# SCH_555-timer-LED-Chaser_2025-11-26.net
KiCad netlist of a schematic drawn in EasyEDA
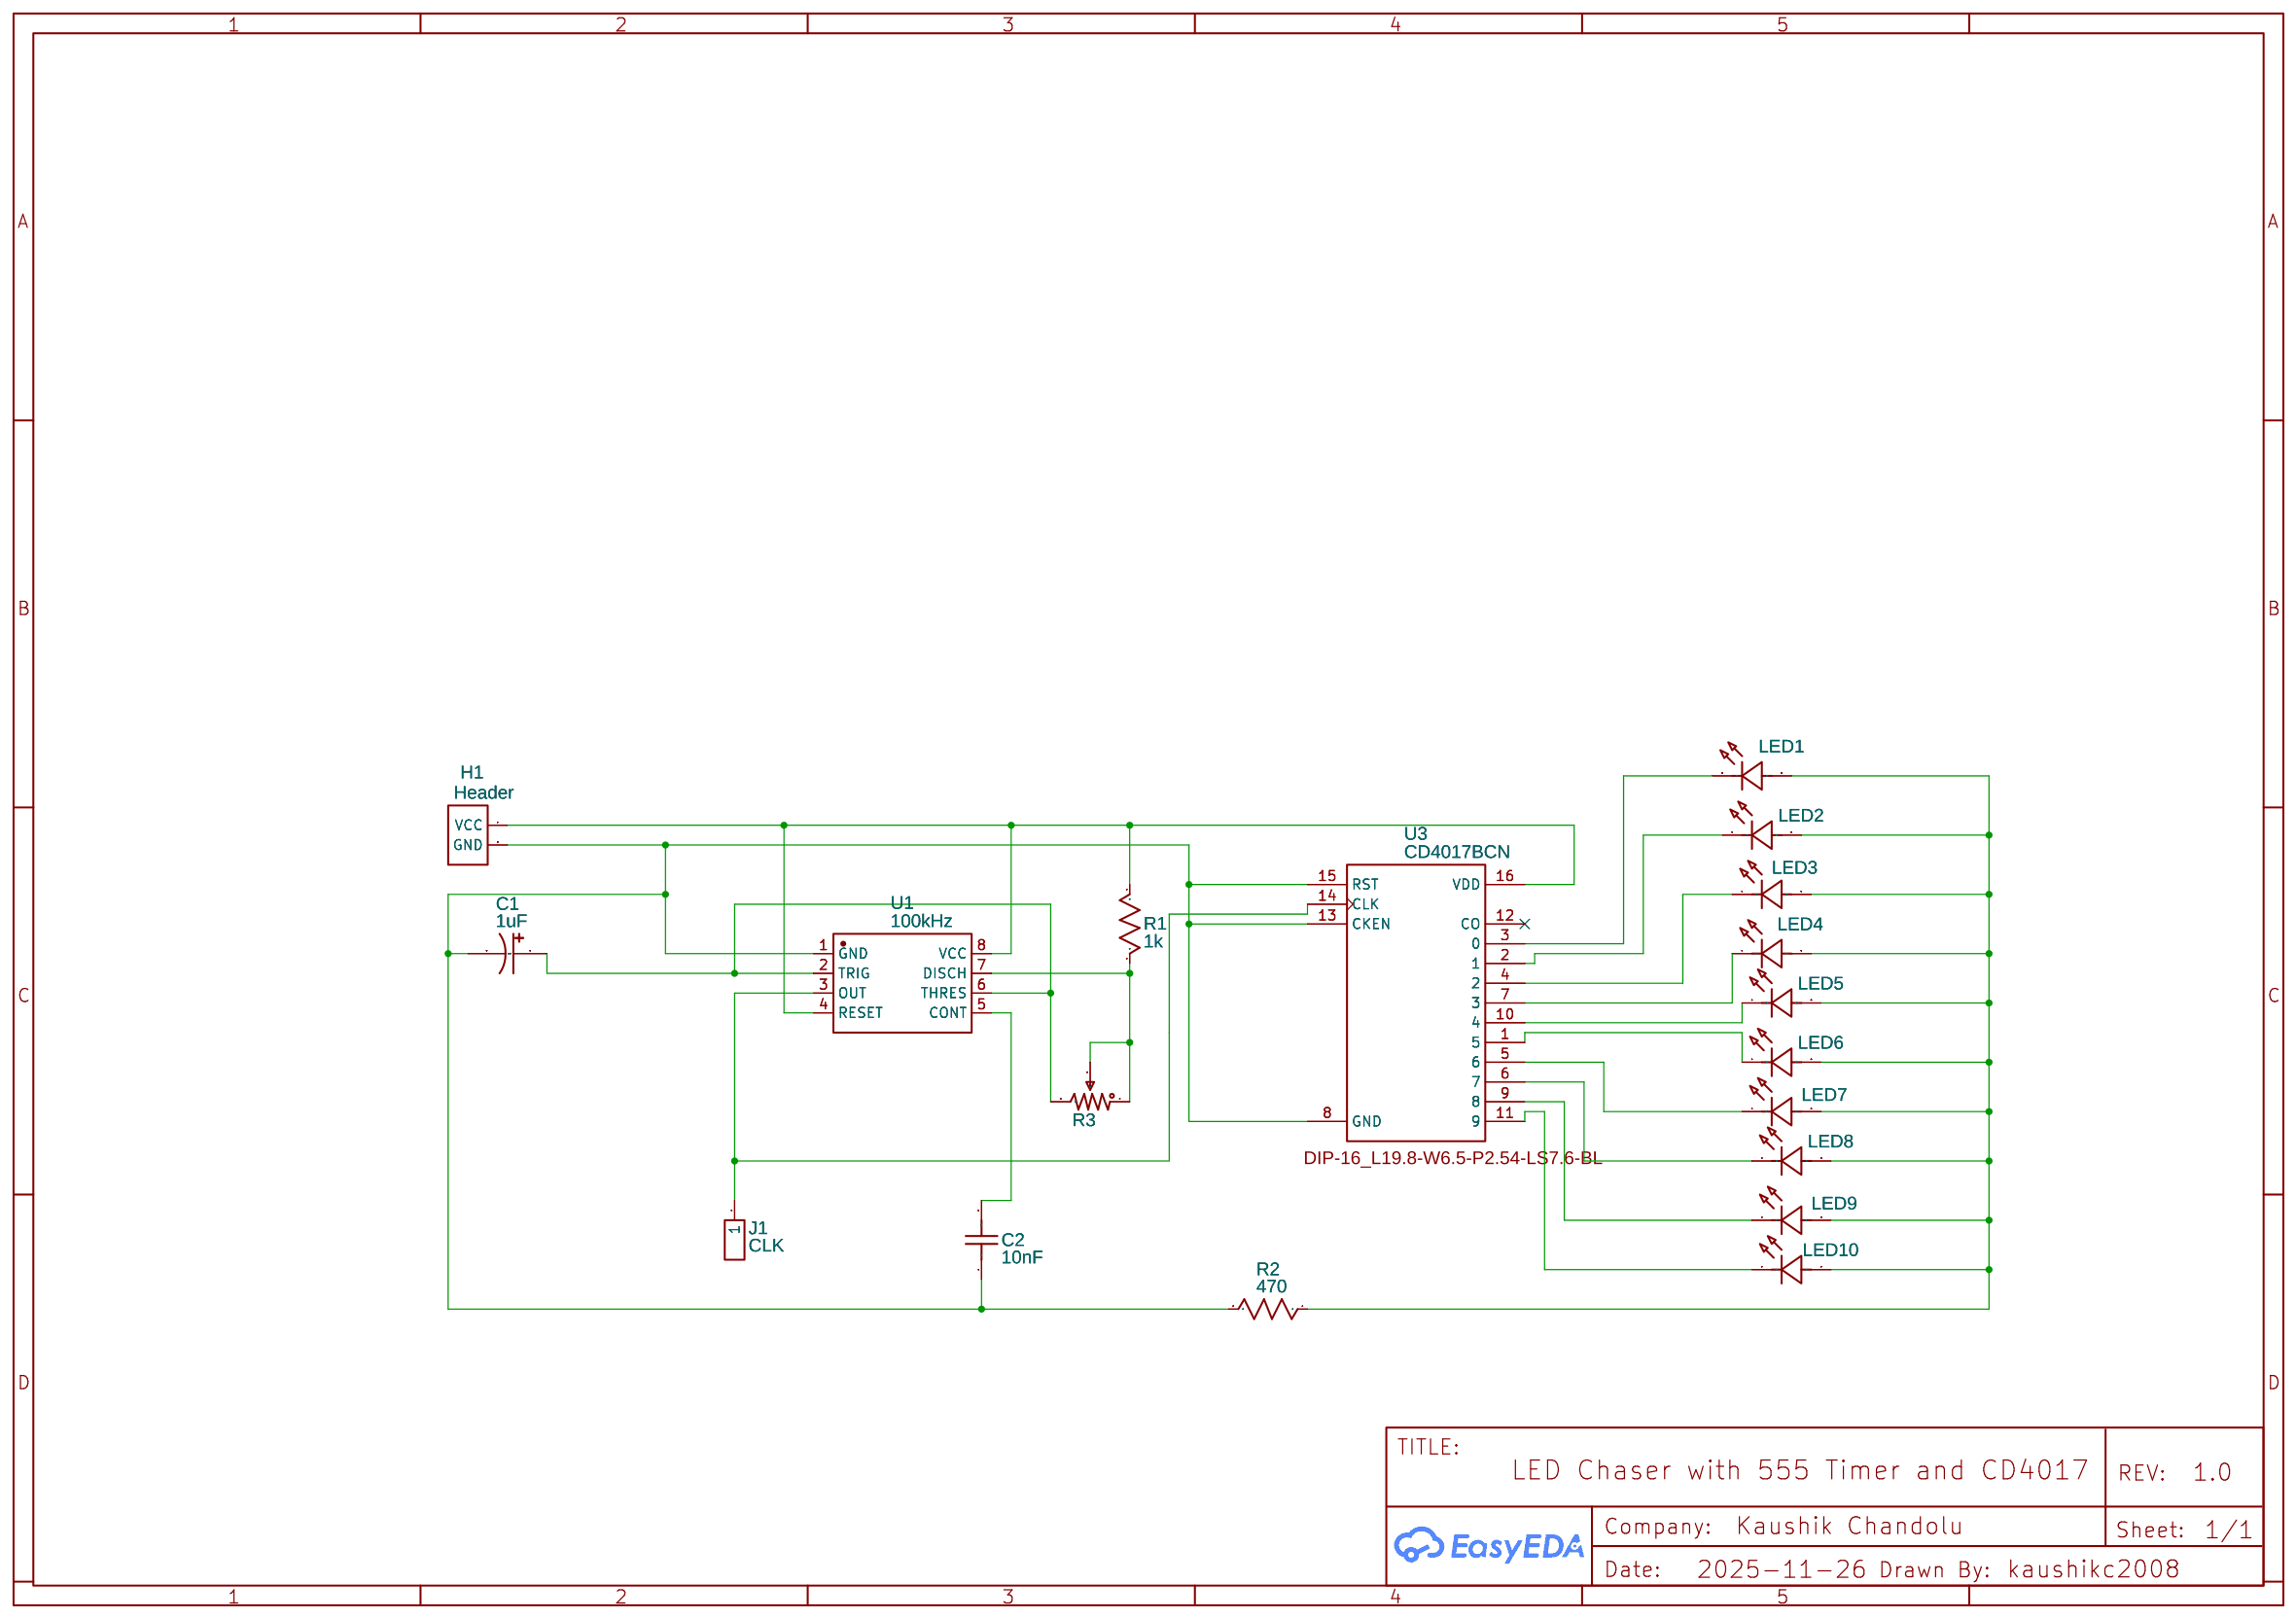
[diagram p0: schematic sheet]

(export (version "E")
  (design (tool "Eeschema 10.0.6"))
  (components
    (comp (ref "C1")
      (value "1uF")
      (fields (field (name "Manufacturer Part") "UVZ1H010MDD") (field (name "Manufacturer") "Nichicon(尼吉康)"))
      (libsource (lib "") (part "UVZ1H010MDD"))
    )
    (comp (ref "C2")
      (value "10nF")
      (fields
        (field (name "Manufacturer Part") "N09F1B103MN0B0S0N0")
        (field (name "Manufacturer") "Songtian Elec")
      )
      (libsource (lib "") (part "CAP 10nF HV"))
    )
    (comp (ref "H1") (value "Header") (libsource (lib "") (part "HEADER-FEMALE-2.54_1X2")))
    (comp (ref "J1") (value "CLK") (libsource (lib "") (part "HDR-M-2.54_1x1")))
    (comp (ref "LED1")
      (value "XL-502UWC")
      (fields (field (name "Manufacturer") "XINGLIGHT(成兴光)"))
      (libsource (lib "") (part "XL-502UWC"))
    )
    (comp (ref "LED2")
      (value "XL-502UWC")
      (fields (field (name "Manufacturer") "XINGLIGHT(成兴光)"))
      (libsource (lib "") (part "XL-502UWC"))
    )
    (comp (ref "LED3")
      (value "XL-502UWC")
      (fields (field (name "Manufacturer") "XINGLIGHT(成兴光)"))
      (libsource (lib "") (part "XL-502UWC"))
    )
    (comp (ref "LED4")
      (value "XL-502UWC")
      (fields (field (name "Manufacturer") "XINGLIGHT(成兴光)"))
      (libsource (lib "") (part "XL-502UWC"))
    )
    (comp (ref "LED5")
      (value "XL-502UWC")
      (fields (field (name "Manufacturer") "XINGLIGHT(成兴光)"))
      (libsource (lib "") (part "XL-502UWC"))
    )
    (comp (ref "LED6")
      (value "XL-502UWC")
      (fields (field (name "Manufacturer") "XINGLIGHT(成兴光)"))
      (libsource (lib "") (part "XL-502UWC"))
    )
    (comp (ref "LED7")
      (value "XL-502UWC")
      (fields (field (name "Manufacturer") "XINGLIGHT(成兴光)"))
      (libsource (lib "") (part "XL-502UWC"))
    )
    (comp (ref "LED8")
      (value "XL-502UWC")
      (fields (field (name "Manufacturer") "XINGLIGHT(成兴光)"))
      (libsource (lib "") (part "XL-502UWC"))
    )
    (comp (ref "LED9")
      (value "XL-502UWC")
      (fields (field (name "Manufacturer") "XINGLIGHT(成兴光)"))
      (libsource (lib "") (part "XL-502UWC"))
    )
    (comp (ref "LED10")
      (value "XL-502UWC")
      (fields (field (name "Manufacturer") "XINGLIGHT(成兴光)"))
      (libsource (lib "") (part "XL-502UWC"))
    )
    (comp (ref "R1")
      (value "1k")
      (fields
        (field (name "Manufacturer Part") "MF1/4W-1KΩ±1%T52")
        (field (name "Manufacturer") "Huaxing Mechanical-Elec.")
      )
      (libsource (lib "") (part "R_0603_US"))
    )
    (comp (ref "R2")
      (value "470")
      (fields (field (name "Manufacturer Part") "?"))
      (libsource (lib "") (part "Resistor"))
    )
    (comp (ref "R3") (value "R_3386P_US") (libsource (lib "") (part "R_3386P_US")))
    (comp (ref "U1")
      (value "100kHz")
      (fields (field (name "Manufacturer Part") "NE555P") (field (name "Manufacturer") "TI(德州仪器)"))
      (libsource (lib "") (part "NE555P"))
    )
    (comp (ref "U3") (value "CD4017BCN") (libsource (lib "") (part "CD4017BCN")))
  )
  (nets
    (net (code "1") (name "Net-(H1-GND)") (class "Default")
      (node (ref "C1") (pin "2") (pinfunction "2_2") (pintype "unspecified"))
      (node (ref "C2") (pin "1") (pinfunction "1_1") (pintype "unspecified"))
      (node (ref "H1") (pin "2") (pinfunction "GND_2") (pintype "unspecified"))
      (node (ref "R2") (pin "2") (pinfunction "2_2") (pintype "unspecified"))
      (node (ref "U1") (pin "1") (pinfunction "GND_1") (pintype "unspecified"))
      (node (ref "U3") (pin "13") (pinfunction "CKEN_13") (pintype "unspecified"))
      (node (ref "U3") (pin "15") (pinfunction "RST_15") (pintype "unspecified"))
      (node (ref "U3") (pin "8") (pinfunction "GND_8") (pintype "unspecified"))
    )
    (net (code "2") (name "Net-(H1-VCC)") (class "Default")
      (node (ref "H1") (pin "1") (pinfunction "VCC_1") (pintype "unspecified"))
      (node (ref "R1") (pin "2") (pinfunction "2_2") (pintype "unspecified"))
      (node (ref "U1") (pin "4") (pinfunction "RESET_4") (pintype "unspecified"))
      (node (ref "U1") (pin "8") (pinfunction "VCC_8") (pintype "unspecified"))
      (node (ref "U3") (pin "16") (pinfunction "VDD_16") (pintype "unspecified"))
    )
    (net (code "3") (name "Net-(LED1-A)") (class "Default")
      (node (ref "LED1") (pin "2") (pinfunction "A_2") (pintype "unspecified"))
      (node (ref "LED10") (pin "2") (pinfunction "A_2") (pintype "unspecified"))
      (node (ref "LED2") (pin "2") (pinfunction "A_2") (pintype "unspecified"))
      (node (ref "LED3") (pin "2") (pinfunction "A_2") (pintype "unspecified"))
      (node (ref "LED4") (pin "2") (pinfunction "A_2") (pintype "unspecified"))
      (node (ref "LED5") (pin "2") (pinfunction "A_2") (pintype "unspecified"))
      (node (ref "LED6") (pin "2") (pinfunction "A_2") (pintype "unspecified"))
      (node (ref "LED7") (pin "2") (pinfunction "A_2") (pintype "unspecified"))
      (node (ref "LED8") (pin "2") (pinfunction "A_2") (pintype "unspecified"))
      (node (ref "LED9") (pin "2") (pinfunction "A_2") (pintype "unspecified"))
      (node (ref "R2") (pin "1") (pinfunction "1_1") (pintype "unspecified"))
    )
    (net (code "4") (name "Net-(LED1-K)") (class "Default")
      (node (ref "LED1") (pin "1") (pinfunction "K_1") (pintype "unspecified"))
      (node (ref "U3") (pin "3") (pinfunction "0_3") (pintype "unspecified"))
    )
    (net (code "5") (name "Net-(LED2-K)") (class "Default")
      (node (ref "LED2") (pin "1") (pinfunction "K_1") (pintype "unspecified"))
      (node (ref "U3") (pin "2") (pinfunction "1_2") (pintype "unspecified"))
    )
    (net (code "6") (name "Net-(LED3-K)") (class "Default")
      (node (ref "LED3") (pin "1") (pinfunction "K_1") (pintype "unspecified"))
      (node (ref "U3") (pin "4") (pinfunction "2_4") (pintype "unspecified"))
    )
    (net (code "7") (name "Net-(LED4-K)") (class "Default")
      (node (ref "LED4") (pin "1") (pinfunction "K_1") (pintype "unspecified"))
      (node (ref "U3") (pin "7") (pinfunction "3_7") (pintype "unspecified"))
    )
    (net (code "8") (name "Net-(LED5-K)") (class "Default")
      (node (ref "LED5") (pin "1") (pinfunction "K_1") (pintype "unspecified"))
      (node (ref "U3") (pin "10") (pinfunction "4_10") (pintype "unspecified"))
    )
    (net (code "9") (name "Net-(LED6-K)") (class "Default")
      (node (ref "LED6") (pin "1") (pinfunction "K_1") (pintype "unspecified"))
      (node (ref "U3") (pin "1") (pinfunction "5_1") (pintype "unspecified"))
    )
    (net (code "10") (name "Net-(LED7-K)") (class "Default")
      (node (ref "LED7") (pin "1") (pinfunction "K_1") (pintype "unspecified"))
      (node (ref "U3") (pin "5") (pinfunction "6_5") (pintype "unspecified"))
    )
    (net (code "11") (name "Net-(LED8-K)") (class "Default")
      (node (ref "LED8") (pin "1") (pinfunction "K_1") (pintype "unspecified"))
      (node (ref "U3") (pin "6") (pinfunction "7_6") (pintype "unspecified"))
    )
    (net (code "12") (name "Net-(LED9-K)") (class "Default")
      (node (ref "LED9") (pin "1") (pinfunction "K_1") (pintype "unspecified"))
      (node (ref "U3") (pin "9") (pinfunction "8_9") (pintype "unspecified"))
    )
    (net (code "13") (name "Net-(LED10-K)") (class "Default")
      (node (ref "LED10") (pin "1") (pinfunction "K_1") (pintype "unspecified"))
      (node (ref "U3") (pin "11") (pinfunction "9_11") (pintype "unspecified"))
    )
    (net (code "14") (name "Net-(U1-CONT)") (class "Default")
      (node (ref "C2") (pin "2") (pinfunction "2_2") (pintype "unspecified"))
      (node (ref "U1") (pin "5") (pinfunction "CONT_5") (pintype "unspecified"))
    )
    (net (code "15") (name "Net-(U1-DISCH)") (class "Default")
      (node (ref "R1") (pin "1") (pinfunction "1_1") (pintype "unspecified"))
      (node (ref "R3") (pin "1") (pinfunction "1_1") (pintype "unspecified"))
      (node (ref "R3") (pin "2") (pinfunction "2_2") (pintype "unspecified"))
      (node (ref "U1") (pin "7") (pinfunction "DISCH_7") (pintype "unspecified"))
    )
    (net (code "16") (name "Net-(U1-OUT)") (class "Default")
      (node (ref "J1") (pin "1") (pinfunction "1_1") (pintype "unspecified"))
      (node (ref "U1") (pin "3") (pinfunction "OUT_3") (pintype "unspecified"))
      (node (ref "U3") (pin "14") (pinfunction "CLK_14") (pintype "unspecified"))
    )
    (net (code "17") (name "Net-(U1-THRES)") (class "Default")
      (node (ref "C1") (pin "1") (pinfunction "1_1") (pintype "unspecified"))
      (node (ref "R3") (pin "3") (pinfunction "3_3") (pintype "unspecified"))
      (node (ref "U1") (pin "2") (pinfunction "TRIG_2") (pintype "unspecified"))
      (node (ref "U1") (pin "6") (pinfunction "THRES_6") (pintype "unspecified"))
    )
    (net (code "18") (name "unconnected-(U3-CO-Pad12)") (class "Default")
      (node (ref "U3") (pin "12") (pinfunction "CO_12") (pintype "unspecified+no_connect"))
    )
  )
)
